# bop_it_sch.net
KiCad netlist of a schematic drawn in Altium Designer
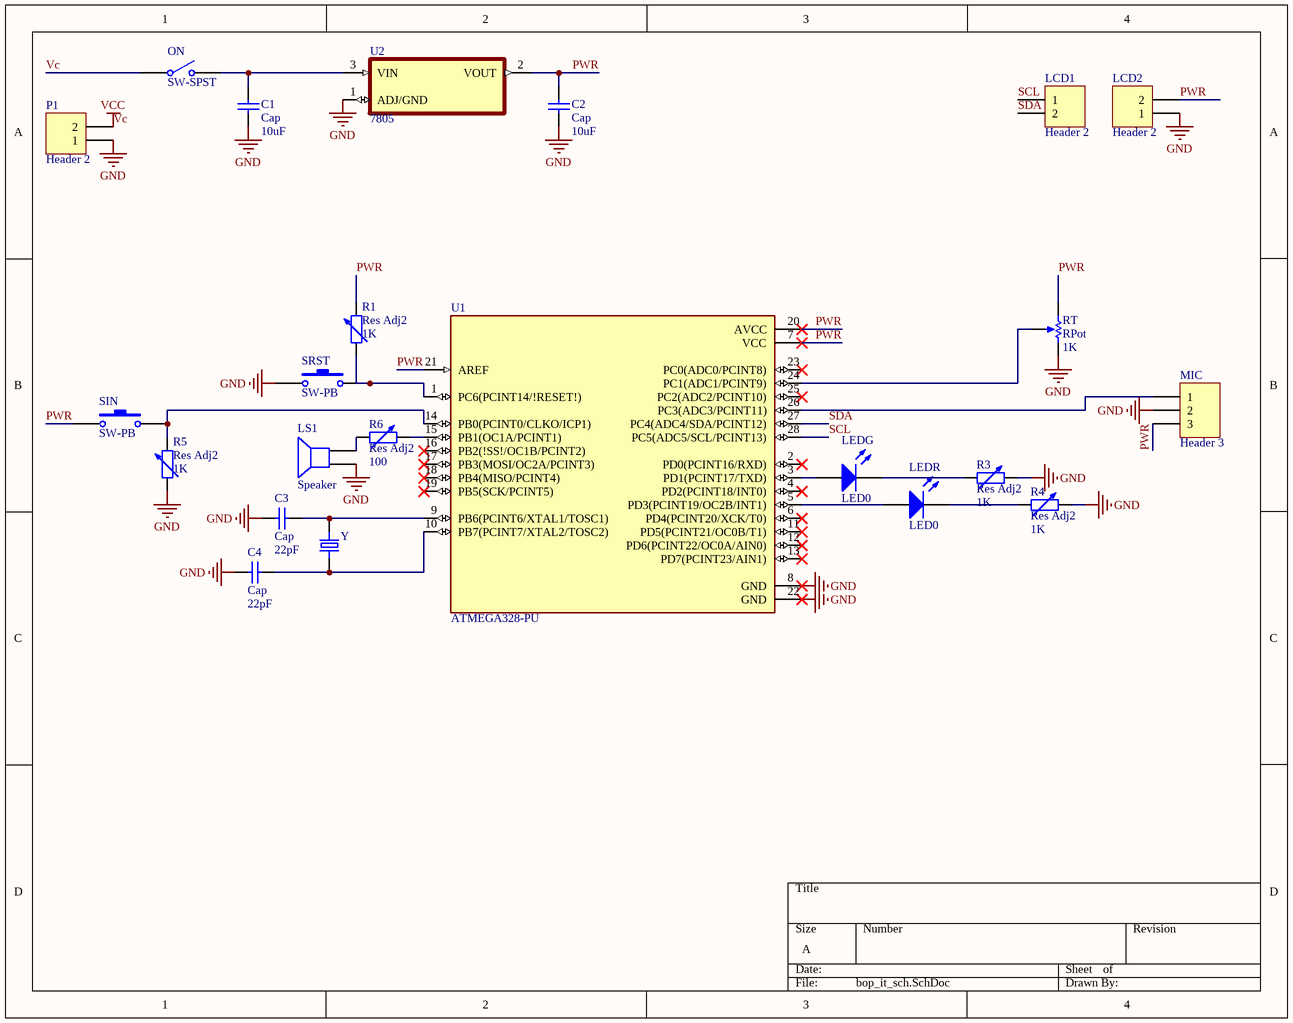
[diagram p0: bop_it_sch.SchDoc]

(export (version "E")
  (design (tool "Eeschema 10.0.6"))
  (components
    (comp (ref "C1")
      (value "Cap")
      (footprint "RAD-0.3")
      (description "Capacitor")
      (fields (field (name "ALTIUM_VALUE") "10uF") (field (name "PUBLISHER") "Altium Limited"))
      (libsource (lib "Miscellaneous Devices") (part "Cap"))
    )
    (comp (ref "C2")
      (value "Cap")
      (footprint "RAD-0.3")
      (description "Capacitor")
      (fields (field (name "ALTIUM_VALUE") "10uF") (field (name "PUBLISHER") "Altium Limited"))
      (libsource (lib "Miscellaneous Devices") (part "Cap"))
    )
    (comp (ref "C3")
      (value "Cap")
      (footprint "RAD-0.3")
      (description "Capacitor")
      (fields (field (name "ALTIUM_VALUE") "22pF") (field (name "PUBLISHER") "Altium Limited"))
      (libsource (lib "Miscellaneous Devices") (part "Cap"))
    )
    (comp (ref "C4")
      (value "Cap")
      (footprint "RAD-0.3")
      (description "Capacitor")
      (fields (field (name "ALTIUM_VALUE") "22pF") (field (name "PUBLISHER") "Altium Limited"))
      (libsource (lib "Miscellaneous Devices") (part "Cap"))
    )
    (comp (ref "LCD1")
      (value "Header 2")
      (footprint "HDR1X2")
      (description "Header, 2-Pin")
      (fields (field (name "PUBLISHER") "Altium Limited"))
      (libsource (lib "Miscellaneous Connectors") (part "Header 2"))
    )
    (comp (ref "LCD2")
      (value "Header 2")
      (footprint "HDR1X2")
      (description "Header, 2-Pin")
      (fields (field (name "PUBLISHER") "Altium Limited"))
      (libsource (lib "") (part "Header 2_1"))
    )
    (comp (ref "LEDG")
      (value "LED0")
      (footprint "LED-0")
      (description "Typical INFRARED GaAs LED")
      (fields (field (name "PUBLISHER") "Altium Limited"))
      (libsource (lib "Miscellaneous Devices") (part "LED0"))
    )
    (comp (ref "LEDR")
      (value "LED0")
      (footprint "LED-0")
      (description "Typical INFRARED GaAs LED")
      (fields (field (name "PUBLISHER") "Altium Limited"))
      (libsource (lib "Miscellaneous Devices") (part "LED0"))
    )
    (comp (ref "LS1")
      (value "Speaker")
      (footprint "PIN2")
      (description "Loudspeaker")
      (fields (field (name "PUBLISHER") "Altium Limited"))
      (libsource (lib "Miscellaneous Devices") (part "Speaker"))
    )
    (comp (ref "MIC")
      (value "Header 3")
      (footprint "HDR1X3")
      (description "Header, 3-Pin")
      (fields (field (name "PUBLISHER") "Altium Limited"))
      (libsource (lib "Miscellaneous Connectors") (part "Header 3"))
    )
    (comp (ref "ON")
      (value "SW-SPST")
      (footprint "SPST-2")
      (description "Single-Pole, Single-Throw Switch")
      (fields (field (name "PUBLISHER") "Altium Limited"))
      (libsource (lib "Miscellaneous Devices") (part "SW-SPST"))
    )
    (comp (ref "P1")
      (value "Header 2")
      (footprint "HDR1X2")
      (description "Header, 2-Pin")
      (fields (field (name "PUBLISHER") "Altium Limited"))
      (libsource (lib "") (part "Header 2_1"))
    )
    (comp (ref "R1")
      (value "Res Adj2")
      (footprint "AXIAL-0.6")
      (description "Variable Resistor")
      (fields (field (name "ALTIUM_VALUE") "1K") (field (name "PUBLISHER") "Altium Limited"))
      (libsource (lib "Miscellaneous Devices") (part "Res Adj2"))
    )
    (comp (ref "R3")
      (value "Res Adj2")
      (footprint "AXIAL-0.6")
      (description "Variable Resistor")
      (fields (field (name "ALTIUM_VALUE") "1K") (field (name "PUBLISHER") "Altium Limited"))
      (libsource (lib "") (part "Res Adj2_1"))
    )
    (comp (ref "R4")
      (value "Res Adj2")
      (footprint "AXIAL-0.6")
      (description "Variable Resistor")
      (fields (field (name "ALTIUM_VALUE") "1K") (field (name "PUBLISHER") "Altium Limited"))
      (libsource (lib "") (part "Res Adj2_1"))
    )
    (comp (ref "R5")
      (value "Res Adj2")
      (footprint "AXIAL-0.6")
      (description "Variable Resistor")
      (fields (field (name "ALTIUM_VALUE") "1K") (field (name "PUBLISHER") "Altium Limited"))
      (libsource (lib "Miscellaneous Devices") (part "Res Adj2"))
    )
    (comp (ref "R6")
      (value "Res Adj2")
      (footprint "AXIAL-0.6")
      (description "Variable Resistor")
      (fields (field (name "ALTIUM_VALUE") "100") (field (name "PUBLISHER") "Altium Limited"))
      (libsource (lib "") (part "Res Adj2_1"))
    )
    (comp (ref "RT")
      (value "RPot")
      (footprint "VR5")
      (description "Potentiometer")
      (fields (field (name "ALTIUM_VALUE") "1K") (field (name "PUBLISHER") "Altium Limited"))
      (libsource (lib "Miscellaneous Devices") (part "RPot"))
    )
    (comp (ref "SIN")
      (value "SW-PB")
      (footprint "SPST-2")
      (description "Switch")
      (fields (field (name "PUBLISHER") "Altium Limited"))
      (libsource (lib "Miscellaneous Devices") (part "SW-PB"))
    )
    (comp (ref "SRST")
      (value "SW-PB")
      (footprint "SPST-2")
      (description "Switch")
      (fields (field (name "PUBLISHER") "Altium Limited"))
      (libsource (lib "Miscellaneous Devices") (part "SW-PB"))
    )
    (comp (ref "U1")
      (value "ATMEGA328-PU")
      (footprint "DIP787W46P254L3467H508Q28")
      (description "AVR AVRÂ® ATmega Microcontroller IC 8-Bit 20MHz 32KB (16K x 16) FLASH 28-PDIP")
      (fields (field (name "MF") "Microchip Technology"))
      (libsource (lib "ATMEGA328-PU") (part "ATMEGA328-PU"))
    )
    (comp (ref "U2")
      (value "7805")
      (footprint "TO254P1054X470X1955-3")
      (description "3-A, 29-V, linear voltage regulator 3-TO-220")
      (fields (field (name "MP") "LM1085IT-5.0") (field (name "MF") "Texas Instruments"))
      (libsource (lib "LM1085IT-5.0") (part "LM1085IT-5.0"))
    )
    (comp (ref "Y")
      (value "ECS-240.0001-18-1X")
      (footprint "XTAL_ECS-200-20-1X")
      (description "Crystals / Oscillators / Resonators 24.00014MHz 18pF")
      (fields (field (name "MF") "ECS International"))
      (libsource (lib "ECS-240.0001-18-1X") (part "ECS-240.0001-18-1X"))
    )
  )
  (nets
    (net (code "1") (name "/PWR") (class "Default")
      (node (ref "C2") (pin "2") (pinfunction "2_2") (pintype "passive"))
      (node (ref "LCD2") (pin "2") (pinfunction "2_2") (pintype "passive"))
      (node (ref "MIC") (pin "3") (pinfunction "3_3") (pintype "passive"))
      (node (ref "R1") (pin "2") (pinfunction "2_2") (pintype "passive"))
      (node (ref "RT") (pin "1") (pinfunction "TOP_1") (pintype "passive"))
      (node (ref "SIN") (pin "1") (pinfunction "1_1") (pintype "passive"))
      (node (ref "U1") (pin "20") (pinfunction "AVCC_20") (pintype "power_in"))
      (node (ref "U1") (pin "21") (pinfunction "AREF_21") (pintype "input"))
      (node (ref "U1") (pin "7") (pinfunction "VCC_7") (pintype "power_in"))
      (node (ref "U2") (pin "2") (pinfunction "VOUT_2") (pintype "output"))
    )
    (net (code "2") (name "/SCL") (class "Default")
      (node (ref "LCD1") (pin "1") (pinfunction "1_1") (pintype "passive"))
      (node (ref "U1") (pin "28") (pinfunction "PC5(ADC5/SCL/PCINT13)_28") (pintype "bidirectional"))
    )
    (net (code "3") (name "/SDA") (class "Default")
      (node (ref "LCD1") (pin "2") (pinfunction "2_2") (pintype "passive"))
      (node (ref "U1") (pin "27") (pinfunction "PC4(ADC4/SDA/PCINT12)_27") (pintype "bidirectional"))
    )
    (net (code "4") (name "GND") (class "Default")
      (node (ref "C1") (pin "1") (pinfunction "1_1") (pintype "passive"))
      (node (ref "C2") (pin "1") (pinfunction "1_1") (pintype "passive"))
      (node (ref "C3") (pin "1") (pinfunction "1_1") (pintype "passive"))
      (node (ref "C4") (pin "1") (pinfunction "1_1") (pintype "passive"))
      (node (ref "LCD2") (pin "1") (pinfunction "1_1") (pintype "passive"))
      (node (ref "LS1") (pin "1") (pinfunction "1_1") (pintype "passive"))
      (node (ref "MIC") (pin "2") (pinfunction "2_2") (pintype "passive"))
      (node (ref "P1") (pin "1") (pinfunction "1_1") (pintype "passive"))
      (node (ref "R3") (pin "2") (pinfunction "2_2") (pintype "passive"))
      (node (ref "R4") (pin "2") (pinfunction "2_2") (pintype "passive"))
      (node (ref "R5") (pin "1") (pinfunction "1_1") (pintype "passive"))
      (node (ref "RT") (pin "2") (pinfunction "BOT_2") (pintype "passive"))
      (node (ref "SRST") (pin "1") (pinfunction "1_1") (pintype "passive"))
      (node (ref "U1") (pin "22") (pinfunction "GND_22") (pintype "power_in"))
      (node (ref "U1") (pin "8") (pinfunction "GND_8") (pintype "power_in"))
      (node (ref "U2") (pin "1") (pinfunction "ADJ/GND_1") (pintype "bidirectional"))
    )
    (net (code "5") (name "Net-(LEDG-A)") (class "Default")
      (node (ref "LEDG") (pin "1") (pinfunction "A_1") (pintype "passive"))
      (node (ref "U1") (pin "3") (pinfunction "PD1(PCINT17/TXD)_3") (pintype "bidirectional"))
    )
    (net (code "6") (name "Net-(LEDG-K)") (class "Default")
      (node (ref "LEDG") (pin "2") (pinfunction "K_2") (pintype "passive"))
      (node (ref "R3") (pin "1") (pinfunction "1_1") (pintype "passive"))
    )
    (net (code "7") (name "Net-(LEDR-A)") (class "Default")
      (node (ref "LEDR") (pin "1") (pinfunction "A_1") (pintype "passive"))
      (node (ref "U1") (pin "5") (pinfunction "PD3(PCINT19/OC2B/INT1)_5") (pintype "bidirectional"))
    )
    (net (code "8") (name "Net-(LEDR-K)") (class "Default")
      (node (ref "LEDR") (pin "2") (pinfunction "K_2") (pintype "passive"))
      (node (ref "R4") (pin "1") (pinfunction "1_1") (pintype "passive"))
    )
    (net (code "9") (name "Net-(LS1-Pad2)") (class "Default")
      (node (ref "LS1") (pin "2") (pinfunction "2_2") (pintype "passive"))
      (node (ref "R6") (pin "1") (pinfunction "1_1") (pintype "passive"))
    )
    (net (code "10") (name "Net-(ON-NO)") (class "Default")
      (node (ref "C1") (pin "2") (pinfunction "2_2") (pintype "passive"))
      (node (ref "ON") (pin "2") (pinfunction "NO_2") (pintype "passive"))
      (node (ref "U2") (pin "3") (pinfunction "VIN_3") (pintype "input"))
    )
    (net (code "11") (name "Net-(RT-TAP)") (class "Default")
      (node (ref "RT") (pin "3") (pinfunction "TAP_3") (pintype "passive"))
      (node (ref "U1") (pin "24") (pinfunction "PC1(ADC1/PCINT9)_24") (pintype "bidirectional"))
    )
    (net (code "12") (name "Net-(U1-PB0(PCINT0{slash}CLKO{slash}ICP1))") (class "Default")
      (node (ref "R5") (pin "2") (pinfunction "2_2") (pintype "passive"))
      (node (ref "SIN") (pin "2") (pinfunction "2_2") (pintype "passive"))
      (node (ref "U1") (pin "14") (pinfunction "PB0(PCINT0/CLKO/ICP1)_14") (pintype "bidirectional"))
    )
    (net (code "13") (name "Net-(U1-PB1(OC1A{slash}PCINT1))") (class "Default")
      (node (ref "R6") (pin "2") (pinfunction "2_2") (pintype "passive"))
      (node (ref "U1") (pin "15") (pinfunction "PB1(OC1A/PCINT1)_15") (pintype "bidirectional"))
    )
    (net (code "14") (name "Net-(U1-PB6(PCINT6{slash}XTAL1{slash}TOSC1))") (class "Default")
      (node (ref "C3") (pin "2") (pinfunction "2_2") (pintype "passive"))
      (node (ref "U1") (pin "9") (pinfunction "PB6(PCINT6/XTAL1/TOSC1)_9") (pintype "bidirectional"))
      (node (ref "Y") (pin "2") (pinfunction "2_2") (pintype "passive"))
    )
    (net (code "15") (name "Net-(U1-PB7(PCINT7{slash}XTAL2{slash}TOSC2))") (class "Default")
      (node (ref "C4") (pin "2") (pinfunction "2_2") (pintype "passive"))
      (node (ref "U1") (pin "10") (pinfunction "PB7(PCINT7/XTAL2/TOSC2)_10") (pintype "bidirectional"))
      (node (ref "Y") (pin "1") (pinfunction "1_1") (pintype "passive"))
    )
    (net (code "16") (name "Net-(U1-PC3(ADC3{slash}PCINT11))") (class "Default")
      (node (ref "MIC") (pin "1") (pinfunction "1_1") (pintype "passive"))
      (node (ref "U1") (pin "26") (pinfunction "PC3(ADC3/PCINT11)_26") (pintype "bidirectional"))
    )
    (net (code "17") (name "Net-(U1-PC6(PCINT14{slash}!RESET!))") (class "Default")
      (node (ref "R1") (pin "1") (pinfunction "1_1") (pintype "passive"))
      (node (ref "SRST") (pin "2") (pinfunction "2_2") (pintype "passive"))
      (node (ref "U1") (pin "1") (pinfunction "PC6(PCINT14/!RESET!)_1") (pintype "bidirectional"))
    )
    (net (code "18") (name "VCC") (class "Default")
      (node (ref "ON") (pin "1") (pinfunction "COMMON_1") (pintype "passive"))
      (node (ref "P1") (pin "2") (pinfunction "2_2") (pintype "passive"))
    )
    (net (code "19") (name "unconnected-(U1-PB2(!SS!{slash}OC1B{slash}PCINT2)-Pad16)") (class "Default")
      (node (ref "U1") (pin "16") (pinfunction "PB2(!SS!/OC1B/PCINT2)_16") (pintype "bidirectional+no_connect"))
    )
    (net (code "20") (name "unconnected-(U1-PB3(MOSI{slash}OC2A{slash}PCINT3)-Pad17)") (class "Default")
      (node (ref "U1") (pin "17") (pinfunction "PB3(MOSI/OC2A/PCINT3)_17") (pintype "bidirectional+no_connect"))
    )
    (net (code "21") (name "unconnected-(U1-PB4(MISO{slash}PCINT4)-Pad18)") (class "Default")
      (node (ref "U1") (pin "18") (pinfunction "PB4(MISO/PCINT4)_18") (pintype "bidirectional+no_connect"))
    )
    (net (code "22") (name "unconnected-(U1-PB5(SCK{slash}PCINT5)-Pad19)") (class "Default")
      (node (ref "U1") (pin "19") (pinfunction "PB5(SCK/PCINT5)_19") (pintype "bidirectional+no_connect"))
    )
    (net (code "23") (name "unconnected-(U1-PC0(ADC0{slash}PCINT8)-Pad23)") (class "Default")
      (node (ref "U1") (pin "23") (pinfunction "PC0(ADC0/PCINT8)_23") (pintype "bidirectional+no_connect"))
    )
    (net (code "24") (name "unconnected-(U1-PC2(ADC2{slash}PCINT10)-Pad25)") (class "Default")
      (node (ref "U1") (pin "25") (pinfunction "PC2(ADC2/PCINT10)_25") (pintype "bidirectional+no_connect"))
    )
    (net (code "25") (name "unconnected-(U1-PD0(PCINT16{slash}RXD)-Pad2)") (class "Default")
      (node (ref "U1") (pin "2") (pinfunction "PD0(PCINT16/RXD)_2") (pintype "bidirectional+no_connect"))
    )
    (net (code "26") (name "unconnected-(U1-PD2(PCINT18{slash}INT0)-Pad4)") (class "Default")
      (node (ref "U1") (pin "4") (pinfunction "PD2(PCINT18/INT0)_4") (pintype "bidirectional+no_connect"))
    )
    (net (code "27") (name "unconnected-(U1-PD4(PCINT20{slash}XCK{slash}T0)-Pad6)") (class "Default")
      (node (ref "U1") (pin "6") (pinfunction "PD4(PCINT20/XCK/T0)_6") (pintype "bidirectional+no_connect"))
    )
    (net (code "28") (name "unconnected-(U1-PD5(PCINT21{slash}OC0B{slash}T1)-Pad11)") (class "Default")
      (node (ref "U1") (pin "11") (pinfunction "PD5(PCINT21/OC0B/T1)_11") (pintype "bidirectional+no_connect"))
    )
    (net (code "29") (name "unconnected-(U1-PD6(PCINT22{slash}OC0A{slash}AIN0)-Pad12)") (class "Default")
      (node (ref "U1") (pin "12") (pinfunction "PD6(PCINT22/OC0A/AIN0)_12") (pintype "bidirectional+no_connect"))
    )
    (net (code "30") (name "unconnected-(U1-PD7(PCINT23{slash}AIN1)-Pad13)") (class "Default")
      (node (ref "U1") (pin "13") (pinfunction "PD7(PCINT23/AIN1)_13") (pintype "bidirectional+no_connect"))
    )
  )
)
